# 8x8r1.net
KiCad netlist of a schematic drawn in EAGLE
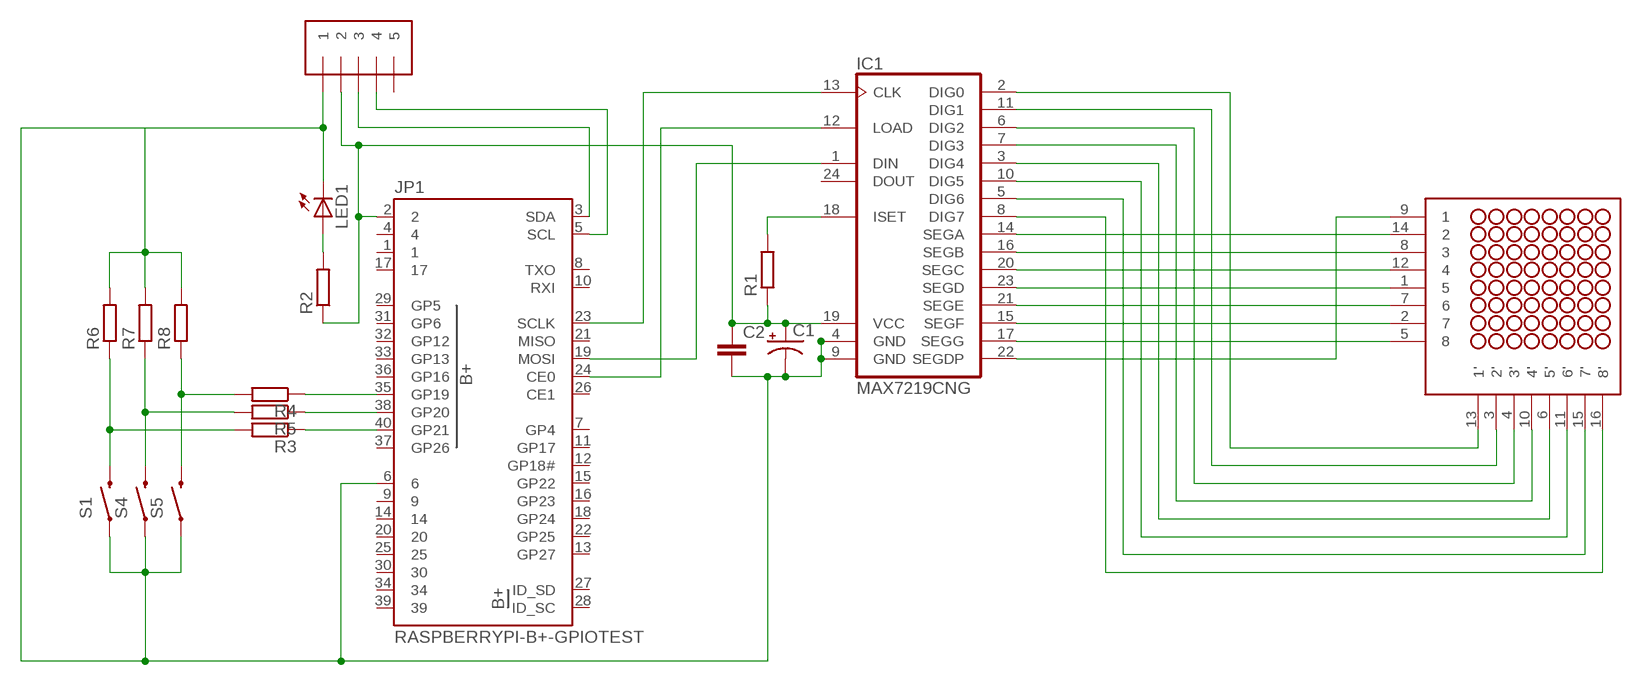
[diagram p0: schematic, sheet 1]

(export (version "E")
  (design (tool "Eeschema 10.0.6"))
  (components
    (comp (ref "C1")
      (value "CPOL-USE2.5-7")
      (footprint "eagle-import:E2,5-7")
      (libsource (lib "eagle-import") (part "CPOL-USE2.5-7"))
    )
    (comp (ref "C2")
      (value "C-EU025-024X044")
      (footprint "eagle-import:C025-024X044")
      (libsource (lib "eagle-import") (part "C-EU025-024X044"))
    )
    (comp (ref "IC1")
      (value "MAX7219CNG")
      (footprint "eagle-import:DIL24-3")
      (fields (field (name "MF") "MAXIM"))
      (libsource (lib "eagle-import") (part "MAX7219CNG"))
    )
    (comp (ref "J1")
      (value "1X5")
      (footprint "eagle-import:1X05-3.5MM")
      (libsource (lib "eagle-import") (part "1X5"))
    )
    (comp (ref "JP1")
      (value "RASPBERRYPI-B+-GPIOTEST")
      (footprint "eagle-import:2X20-SHROUDED")
      (libsource (lib "eagle-import") (part "RASPBERRYPI-B+-GPIOTEST"))
    )
    (comp (ref "LED1")
      (value "LED3MM")
      (footprint "eagle-import:LED3MM")
      (libsource (lib "eagle-import") (part "LED3MM"))
    )
    (comp (ref "R1")
      (value "R-EU_0204/7")
      (footprint "eagle-import:0204_7")
      (libsource (lib "eagle-import") (part "R-EU_0204/7"))
    )
    (comp (ref "R2")
      (value "R-EU_0204/7")
      (footprint "eagle-import:0204_7")
      (libsource (lib "eagle-import") (part "R-EU_0204/7"))
    )
    (comp (ref "R3")
      (value "R-EU_0204/7")
      (footprint "eagle-import:0204_7")
      (libsource (lib "eagle-import") (part "R-EU_0204/7"))
    )
    (comp (ref "R4")
      (value "R-EU_0204/7")
      (footprint "eagle-import:0204_7")
      (libsource (lib "eagle-import") (part "R-EU_0204/7"))
    )
    (comp (ref "R5")
      (value "R-EU_0204/7")
      (footprint "eagle-import:0204_7")
      (libsource (lib "eagle-import") (part "R-EU_0204/7"))
    )
    (comp (ref "R6")
      (value "R-EU_0204/7")
      (footprint "eagle-import:0204_7")
      (libsource (lib "eagle-import") (part "R-EU_0204/7"))
    )
    (comp (ref "R7")
      (value "R-EU_0204/7")
      (footprint "eagle-import:0204_7")
      (libsource (lib "eagle-import") (part "R-EU_0204/7"))
    )
    (comp (ref "R8")
      (value "R-EU_0204/7")
      (footprint "eagle-import:0204_7")
      (libsource (lib "eagle-import") (part "R-EU_0204/7"))
    )
    (comp (ref "S1")
      (value "SPARKFUN-ELECTROMECHANICAL_SWITCH-MOMENTARY-2PTH")
      (footprint "eagle-import:SPARKFUN-ELECTROMECHANICAL_TACTILE-PTH")
      (libsource (lib "eagle-import") (part "SPARKFUN-ELECTROMECHANICAL_SWITCH-MOMENTARY-2PTH"))
    )
    (comp (ref "S4")
      (value "SPARKFUN-ELECTROMECHANICAL_SWITCH-MOMENTARY-2PTH")
      (footprint "eagle-import:SPARKFUN-ELECTROMECHANICAL_TACTILE-PTH")
      (libsource (lib "eagle-import") (part "SPARKFUN-ELECTROMECHANICAL_SWITCH-MOMENTARY-2PTH"))
    )
    (comp (ref "S5")
      (value "SPARKFUN-ELECTROMECHANICAL_SWITCH-MOMENTARY-2PTH")
      (footprint "eagle-import:SPARKFUN-ELECTROMECHANICAL_TACTILE-PTH")
      (libsource (lib "eagle-import") (part "SPARKFUN-ELECTROMECHANICAL_SWITCH-MOMENTARY-2PTH"))
    )
    (comp (ref "U$1")
      (value "NFM-12881BG-11")
      (footprint "eagle-import:NFM-12881BG-11")
      (libsource (lib "eagle-import") (part "NFM-12881BG-11"))
    )
  )
  (nets
    (net (code "1") (name "/1") (class "Default")
      (node (ref "JP1") (pin "1") (pinfunction "1_1") (pintype "power_in"))
    )
    (net (code "2") (name "/4") (class "Default")
      (node (ref "JP1") (pin "4") (pinfunction "4_4") (pintype "power_in"))
    )
    (net (code "3") (name "/9") (class "Default")
      (node (ref "JP1") (pin "9") (pinfunction "9_9") (pintype "power_in"))
    )
    (net (code "4") (name "/14") (class "Default")
      (node (ref "JP1") (pin "14") (pinfunction "14_14") (pintype "power_in"))
    )
    (net (code "5") (name "/17") (class "Default")
      (node (ref "JP1") (pin "17") (pinfunction "17_17") (pintype "power_in"))
    )
    (net (code "6") (name "/20") (class "Default")
      (node (ref "JP1") (pin "20") (pinfunction "20_20") (pintype "power_in"))
    )
    (net (code "7") (name "/25") (class "Default")
      (node (ref "JP1") (pin "25") (pinfunction "25_25") (pintype "power_in"))
    )
    (net (code "8") (name "/30") (class "Default")
      (node (ref "JP1") (pin "30") (pinfunction "30_30") (pintype "power_in"))
    )
    (net (code "9") (name "/34") (class "Default")
      (node (ref "JP1") (pin "34") (pinfunction "34_34") (pintype "power_in"))
    )
    (net (code "10") (name "/39") (class "Default")
      (node (ref "JP1") (pin "39") (pinfunction "39_39") (pintype "power_in"))
    )
    (net (code "11") (name "Net-(IC1-CLK)") (class "Default")
      (node (ref "IC1") (pin "13") (pinfunction "CLK_13") (pintype "input"))
      (node (ref "JP1") (pin "23") (pinfunction "SCLK_23") (pintype "output"))
    )
    (net (code "12") (name "Net-(IC1-DIG0)") (class "Default")
      (node (ref "IC1") (pin "2") (pinfunction "DIG0_2") (pintype "output"))
      (node (ref "U$1") (pin "13") (pinfunction "1'_13") (pintype "output"))
    )
    (net (code "13") (name "Net-(IC1-DIG1)") (class "Default")
      (node (ref "IC1") (pin "11") (pinfunction "DIG1_11") (pintype "output"))
      (node (ref "U$1") (pin "3") (pinfunction "2'_3") (pintype "output"))
    )
    (net (code "14") (name "Net-(IC1-DIG2)") (class "Default")
      (node (ref "IC1") (pin "6") (pinfunction "DIG2_6") (pintype "output"))
      (node (ref "U$1") (pin "4") (pinfunction "3'_4") (pintype "output"))
    )
    (net (code "15") (name "Net-(IC1-DIG3)") (class "Default")
      (node (ref "IC1") (pin "7") (pinfunction "DIG3_7") (pintype "output"))
      (node (ref "U$1") (pin "10") (pinfunction "4'_10") (pintype "output"))
    )
    (net (code "16") (name "Net-(IC1-DIG4)") (class "Default")
      (node (ref "IC1") (pin "3") (pinfunction "DIG4_3") (pintype "output"))
      (node (ref "U$1") (pin "6") (pinfunction "5'_6") (pintype "output"))
    )
    (net (code "17") (name "Net-(IC1-DIG5)") (class "Default")
      (node (ref "IC1") (pin "10") (pinfunction "DIG5_10") (pintype "output"))
      (node (ref "U$1") (pin "11") (pinfunction "6'_11") (pintype "output"))
    )
    (net (code "18") (name "Net-(IC1-DIG6)") (class "Default")
      (node (ref "IC1") (pin "5") (pinfunction "DIG6_5") (pintype "output"))
      (node (ref "U$1") (pin "15") (pinfunction "7'_15") (pintype "output"))
    )
    (net (code "19") (name "Net-(IC1-DIG7)") (class "Default")
      (node (ref "IC1") (pin "8") (pinfunction "DIG7_8") (pintype "output"))
      (node (ref "U$1") (pin "16") (pinfunction "8'_16") (pintype "output"))
    )
    (net (code "20") (name "Net-(IC1-DIN)") (class "Default")
      (node (ref "IC1") (pin "1") (pinfunction "DIN_1") (pintype "input"))
      (node (ref "JP1") (pin "19") (pinfunction "MOSI_19") (pintype "output"))
    )
    (net (code "21") (name "Net-(IC1-ISET)") (class "Default")
      (node (ref "IC1") (pin "18") (pinfunction "ISET_18") (pintype "input"))
      (node (ref "R1") (pin "2") (pinfunction "2_2") (pintype "passive"))
    )
    (net (code "22") (name "Net-(IC1-LOAD)") (class "Default")
      (node (ref "IC1") (pin "12") (pinfunction "LOAD_12") (pintype "input"))
      (node (ref "JP1") (pin "24") (pinfunction "CE0_24") (pintype "output"))
    )
    (net (code "23") (name "Net-(IC1-SEGA)") (class "Default")
      (node (ref "IC1") (pin "14") (pinfunction "SEGA_14") (pintype "output"))
      (node (ref "U$1") (pin "14") (pinfunction "2_14") (pintype "input"))
    )
    (net (code "24") (name "Net-(IC1-SEGB)") (class "Default")
      (node (ref "IC1") (pin "16") (pinfunction "SEGB_16") (pintype "output"))
      (node (ref "U$1") (pin "8") (pinfunction "3_8") (pintype "input"))
    )
    (net (code "25") (name "Net-(IC1-SEGC)") (class "Default")
      (node (ref "IC1") (pin "20") (pinfunction "SEGC_20") (pintype "output"))
      (node (ref "U$1") (pin "12") (pinfunction "4_12") (pintype "input"))
    )
    (net (code "26") (name "Net-(IC1-SEGD)") (class "Default")
      (node (ref "IC1") (pin "23") (pinfunction "SEGD_23") (pintype "output"))
      (node (ref "U$1") (pin "1") (pinfunction "5_1") (pintype "input"))
    )
    (net (code "27") (name "Net-(IC1-SEGDP)") (class "Default")
      (node (ref "IC1") (pin "22") (pinfunction "SEGDP_22") (pintype "output"))
      (node (ref "U$1") (pin "9") (pinfunction "1_9") (pintype "input"))
    )
    (net (code "28") (name "Net-(IC1-SEGE)") (class "Default")
      (node (ref "IC1") (pin "21") (pinfunction "SEGE_21") (pintype "output"))
      (node (ref "U$1") (pin "7") (pinfunction "6_7") (pintype "input"))
    )
    (net (code "29") (name "Net-(IC1-SEGF)") (class "Default")
      (node (ref "IC1") (pin "15") (pinfunction "SEGF_15") (pintype "output"))
      (node (ref "U$1") (pin "2") (pinfunction "7_2") (pintype "input"))
    )
    (net (code "30") (name "Net-(IC1-SEGG)") (class "Default")
      (node (ref "IC1") (pin "17") (pinfunction "SEGG_17") (pintype "output"))
      (node (ref "U$1") (pin "5") (pinfunction "8_5") (pintype "input"))
    )
    (net (code "31") (name "Net-(IC1-VCC)") (class "Default")
      (node (ref "C1") (pin "+") (pinfunction "+_+") (pintype "passive"))
      (node (ref "C2") (pin "1") (pinfunction "1_1") (pintype "passive"))
      (node (ref "IC1") (pin "19") (pinfunction "VCC_19") (pintype "power_in"))
      (node (ref "J1") (pin "2") (pinfunction "2_2") (pintype "passive"))
      (node (ref "JP1") (pin "2") (pinfunction "2_2") (pintype "power_in"))
      (node (ref "R1") (pin "1") (pinfunction "1_1") (pintype "passive"))
      (node (ref "R2") (pin "1") (pinfunction "1_1") (pintype "passive"))
    )
    (net (code "32") (name "Net-(JP1-GP19)") (class "Default")
      (node (ref "JP1") (pin "35") (pinfunction "GP19_35") (pintype "bidirectional"))
      (node (ref "R4") (pin "1") (pinfunction "1_1") (pintype "passive"))
    )
    (net (code "33") (name "Net-(JP1-GP20)") (class "Default")
      (node (ref "JP1") (pin "38") (pinfunction "GP20_38") (pintype "bidirectional"))
      (node (ref "R5") (pin "1") (pinfunction "1_1") (pintype "passive"))
    )
    (net (code "34") (name "Net-(JP1-GP21)") (class "Default")
      (node (ref "JP1") (pin "40") (pinfunction "GP21_40") (pintype "bidirectional"))
      (node (ref "R3") (pin "1") (pinfunction "1_1") (pintype "passive"))
    )
    (net (code "35") (name "Net-(JP1-SCL)") (class "Default")
      (node (ref "J1") (pin "4") (pinfunction "4_4") (pintype "passive"))
      (node (ref "JP1") (pin "5") (pinfunction "SCL_5") (pintype "bidirectional"))
    )
    (net (code "36") (name "Net-(JP1-SDA)") (class "Default")
      (node (ref "J1") (pin "3") (pinfunction "3_3") (pintype "passive"))
      (node (ref "JP1") (pin "3") (pinfunction "SDA_3") (pintype "bidirectional"))
    )
    (net (code "37") (name "Net-(LED1-C)") (class "Default")
      (node (ref "C1") (pin "-") (pinfunction "-_-") (pintype "passive"))
      (node (ref "C2") (pin "2") (pinfunction "2_2") (pintype "passive"))
      (node (ref "IC1") (pin "4") (pinfunction "GND_4") (pintype "power_in"))
      (node (ref "IC1") (pin "9") (pinfunction "GND_9") (pintype "power_in"))
      (node (ref "J1") (pin "1") (pinfunction "1_1") (pintype "passive"))
      (node (ref "JP1") (pin "6") (pinfunction "6_6") (pintype "power_in"))
      (node (ref "LED1") (pin "K") (pinfunction "C_K") (pintype "passive"))
      (node (ref "R6") (pin "2") (pinfunction "2_2") (pintype "passive"))
      (node (ref "R7") (pin "2") (pinfunction "2_2") (pintype "passive"))
      (node (ref "R8") (pin "2") (pinfunction "2_2") (pintype "passive"))
      (node (ref "S1") (pin "1") (pinfunction "1_1") (pintype "passive"))
      (node (ref "S4") (pin "1") (pinfunction "1_1") (pintype "passive"))
      (node (ref "S5") (pin "1") (pinfunction "1_1") (pintype "passive"))
    )
    (net (code "38") (name "Net-(LED1-PadA)") (class "Default")
      (node (ref "LED1") (pin "A") (pinfunction "A_A") (pintype "passive"))
      (node (ref "R2") (pin "2") (pinfunction "2_2") (pintype "passive"))
    )
    (net (code "39") (name "Net-(S1-2)") (class "Default")
      (node (ref "R3") (pin "2") (pinfunction "2_2") (pintype "passive"))
      (node (ref "R6") (pin "1") (pinfunction "1_1") (pintype "passive"))
      (node (ref "S1") (pin "3") (pinfunction "2_3") (pintype "passive"))
    )
    (net (code "40") (name "Net-(S4-2)") (class "Default")
      (node (ref "R5") (pin "2") (pinfunction "2_2") (pintype "passive"))
      (node (ref "R7") (pin "1") (pinfunction "1_1") (pintype "passive"))
      (node (ref "S4") (pin "3") (pinfunction "2_3") (pintype "passive"))
    )
    (net (code "41") (name "Net-(S5-2)") (class "Default")
      (node (ref "R4") (pin "2") (pinfunction "2_2") (pintype "passive"))
      (node (ref "R8") (pin "1") (pinfunction "1_1") (pintype "passive"))
      (node (ref "S5") (pin "3") (pinfunction "2_3") (pintype "passive"))
    )
    (net (code "42") (name "unconnected-(IC1-DOUT-Pad24)") (class "Default")
      (node (ref "IC1") (pin "24") (pinfunction "DOUT_24") (pintype "output"))
    )
    (net (code "43") (name "unconnected-(J1-Pad5)") (class "Default")
      (node (ref "J1") (pin "5") (pinfunction "5_5") (pintype "passive"))
    )
    (net (code "44") (name "unconnected-(JP1-CE1-Pad26)") (class "Default")
      (node (ref "JP1") (pin "26") (pinfunction "CE1_26") (pintype "output"))
    )
    (net (code "45") (name "unconnected-(JP1-GP4-Pad7)") (class "Default")
      (node (ref "JP1") (pin "7") (pinfunction "GP4_7") (pintype "bidirectional"))
    )
    (net (code "46") (name "unconnected-(JP1-GP5-Pad29)") (class "Default")
      (node (ref "JP1") (pin "29") (pinfunction "GP5_29") (pintype "bidirectional"))
    )
    (net (code "47") (name "unconnected-(JP1-GP6-Pad31)") (class "Default")
      (node (ref "JP1") (pin "31") (pinfunction "GP6_31") (pintype "bidirectional"))
    )
    (net (code "48") (name "unconnected-(JP1-GP12-Pad32)") (class "Default")
      (node (ref "JP1") (pin "32") (pinfunction "GP12_32") (pintype "bidirectional"))
    )
    (net (code "49") (name "unconnected-(JP1-GP13-Pad33)") (class "Default")
      (node (ref "JP1") (pin "33") (pinfunction "GP13_33") (pintype "bidirectional"))
    )
    (net (code "50") (name "unconnected-(JP1-GP16-Pad36)") (class "Default")
      (node (ref "JP1") (pin "36") (pinfunction "GP16_36") (pintype "bidirectional"))
    )
    (net (code "51") (name "unconnected-(JP1-GP17-Pad11)") (class "Default")
      (node (ref "JP1") (pin "11") (pinfunction "GP17_11") (pintype "bidirectional"))
    )
    (net (code "52") (name "unconnected-(JP1-GP18#-Pad12)") (class "Default")
      (node (ref "JP1") (pin "12") (pinfunction "GP18#_12") (pintype "bidirectional"))
    )
    (net (code "53") (name "unconnected-(JP1-GP22-Pad15)") (class "Default")
      (node (ref "JP1") (pin "15") (pinfunction "GP22_15") (pintype "bidirectional"))
    )
    (net (code "54") (name "unconnected-(JP1-GP23-Pad16)") (class "Default")
      (node (ref "JP1") (pin "16") (pinfunction "GP23_16") (pintype "bidirectional"))
    )
    (net (code "55") (name "unconnected-(JP1-GP24-Pad18)") (class "Default")
      (node (ref "JP1") (pin "18") (pinfunction "GP24_18") (pintype "bidirectional"))
    )
    (net (code "56") (name "unconnected-(JP1-GP25-Pad22)") (class "Default")
      (node (ref "JP1") (pin "22") (pinfunction "GP25_22") (pintype "bidirectional"))
    )
    (net (code "57") (name "unconnected-(JP1-GP26-Pad37)") (class "Default")
      (node (ref "JP1") (pin "37") (pinfunction "GP26_37") (pintype "bidirectional"))
    )
    (net (code "58") (name "unconnected-(JP1-GP27-Pad13)") (class "Default")
      (node (ref "JP1") (pin "13") (pinfunction "GP27_13") (pintype "bidirectional"))
    )
    (net (code "59") (name "unconnected-(JP1-ID_SC-Pad28)") (class "Default")
      (node (ref "JP1") (pin "28") (pinfunction "ID_SC_28") (pintype "bidirectional"))
    )
    (net (code "60") (name "unconnected-(JP1-ID_SD-Pad27)") (class "Default")
      (node (ref "JP1") (pin "27") (pinfunction "ID_SD_27") (pintype "bidirectional"))
    )
    (net (code "61") (name "unconnected-(JP1-MISO-Pad21)") (class "Default")
      (node (ref "JP1") (pin "21") (pinfunction "MISO_21") (pintype "input"))
    )
    (net (code "62") (name "unconnected-(JP1-RXI-Pad10)") (class "Default")
      (node (ref "JP1") (pin "10") (pinfunction "RXI_10") (pintype "input"))
    )
    (net (code "63") (name "unconnected-(JP1-TXO-Pad8)") (class "Default")
      (node (ref "JP1") (pin "8") (pinfunction "TXO_8") (pintype "output"))
    )
  )
)
